# mcu_power_supply.net
KiCad netlist of a schematic drawn in Altium Designer
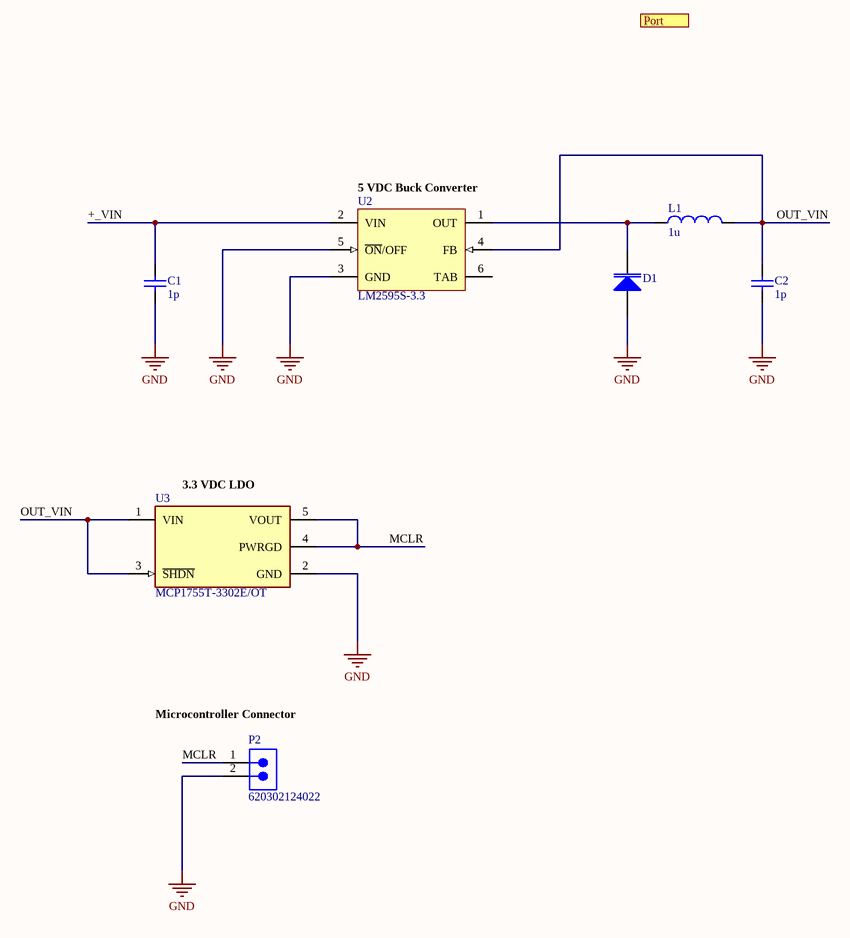
[diagram p0: mcu_power_supply.SchDoc]

(export (version "E")
  (design (tool "Eeschema 10.0.6"))
  (components
    (comp (ref "C1")
      (value "1p")
      (description "Capacitor")
      (libsource (lib "Simulation Generic Components") (part "Capacitor"))
    )
    (comp (ref "C2")
      (value "1p")
      (description "Capacitor")
      (libsource (lib "Simulation Generic Components") (part "Capacitor"))
    )
    (comp (ref "D1") (value "Varactor") (libsource (lib "Simulation Generic Components") (part "Varactor")))
    (comp (ref "L1")
      (value "1u")
      (description "Inductor")
      (libsource (lib "Simulation Generic Components") (part "Inductor"))
    )
    (comp (ref "P2")
      (value "620302124022")
      (footprint "620302124022")
      (libsource (lib "Altium Content Vault") (part "Header_Male_1R_02P"))
    )
    (comp (ref "U2")
      (value "LM2595S-3.3")
      (footprint "KTT0005B_L")
      (description "SIMPLE SWITCHER® Power Converter 150 KHz 1A Step-Down Voltage Regulator, 5-pin TO-263")
      (fields (field (name "MANUFACTURER") "Texas Instruments"))
      (libsource (lib "Altium Content Vault") (part "PM-REG-LM2595S-12"))
    )
    (comp (ref "U3")
      (value "MCP1755T-3302E/OT")
      (footprint "FP-C04-091-OT-MFG")
      (description "IC REG LINEAR 3.3V 300MA SOT23-5")
      (fields (field (name "TOLERANCE") "2%"))
      (libsource (lib "Altium Content Vault") (part "a00d8184c85326696e59f98a1945b30"))
    )
  )
  (nets
    (net (code "1") (name "/+_VIN") (class "Default")
      (node (ref "C1") (pin "2") (pinfunction "2_2") (pintype "passive"))
      (node (ref "U2") (pin "2") (pinfunction "VIN_2") (pintype "power_in"))
    )
    (net (code "2") (name "/MCLR") (class "Default")
      (node (ref "P2") (pin "1") (pinfunction "1_1") (pintype "passive"))
      (node (ref "U3") (pin "4") (pinfunction "PWRGD_4") (pintype "passive"))
      (node (ref "U3") (pin "5") (pinfunction "VOUT_5") (pintype "power_in"))
    )
    (net (code "3") (name "/OUT_VIN") (class "Default")
      (node (ref "C2") (pin "2") (pinfunction "2_2") (pintype "passive"))
      (node (ref "L1") (pin "2") (pinfunction "2_2") (pintype "passive"))
      (node (ref "U2") (pin "4") (pinfunction "FB_4") (pintype "input"))
      (node (ref "U3") (pin "1") (pinfunction "VIN_1") (pintype "power_in"))
      (node (ref "U3") (pin "3") (pinfunction "~{SHDN}_3") (pintype "input"))
    )
    (net (code "5") (name "GND") (class "Default")
      (node (ref "C1") (pin "1") (pinfunction "1_1") (pintype "passive"))
      (node (ref "C2") (pin "1") (pinfunction "1_1") (pintype "passive"))
      (node (ref "D1") (pin "3") (pinfunction "A_3") (pintype "passive"))
      (node (ref "P2") (pin "2") (pinfunction "2_2") (pintype "passive"))
      (node (ref "U2") (pin "3") (pinfunction "GND_3") (pintype "power_in"))
      (node (ref "U2") (pin "5") (pinfunction "~{ON}/OFF_5") (pintype "input"))
      (node (ref "U3") (pin "2") (pinfunction "GND_2") (pintype "power_in"))
    )
    (net (code "6") (name "Net-(D1-K)") (class "Default")
      (node (ref "D1") (pin "1") (pinfunction "K_1") (pintype "passive"))
      (node (ref "L1") (pin "1") (pinfunction "1_1") (pintype "passive"))
      (node (ref "U2") (pin "1") (pinfunction "OUT_1") (pintype "power_in"))
    )
    (net (code "7") (name "unconnected-(U2-TAB-Pad6)") (class "Default")
      (node (ref "U2") (pin "6") (pinfunction "TAB_6") (pintype "power_in"))
    )
  )
)
